# fuente.net
KiCad netlist of a schematic drawn in Altium Designer
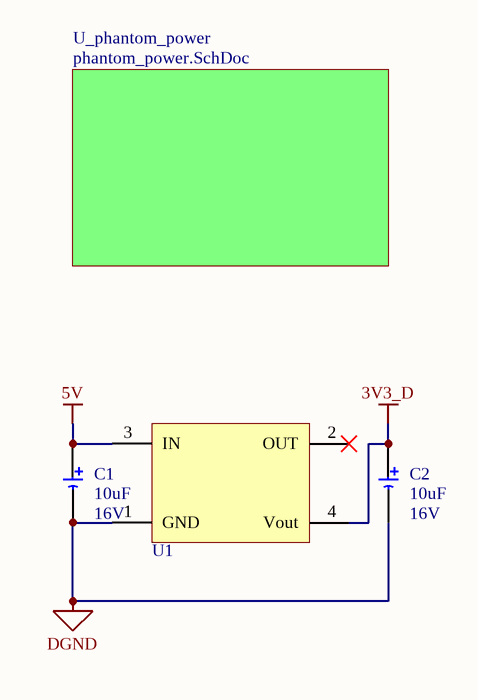
[diagram p0: fuente.SchDoc]

(export (version "E")
  (design (tool "Eeschema 10.0.6"))
  (components
    (comp (ref "C1")
      (value "Capacitor polarizado")
      (footprint "CAP_Electrolytic")
      (fields (field (name "VALOR") "10uF") (field (name "TENSION") "16V"))
      (libsource (lib "sch_comunes") (part "Capacitor polarizado"))
    )
    (comp (ref "C2")
      (value "Capacitor polarizado")
      (footprint "CAP_Electrolytic")
      (fields (field (name "VALOR") "10uF") (field (name "TENSION") "16V"))
      (libsource (lib "sch_comunes") (part "Capacitor polarizado"))
    )
    (comp (ref "U1")
      (value "LM1117")
      (footprint "SOT223")
      (description "LDO Regulator")
      (libsource (lib "Sch_Reguladores") (part "LM1117"))
    )
  )
  (nets
    (net (code "1") (name "3V3_D") (class "Default")
      (node (ref "C2") (pin "1") (pinfunction "1_1") (pintype "passive"))
      (node (ref "U1") (pin "4") (pinfunction "Vout_4") (pintype "passive"))
    )
    (net (code "2") (name "5V") (class "Default")
      (node (ref "C1") (pin "1") (pinfunction "1_1") (pintype "passive"))
      (node (ref "U1") (pin "3") (pinfunction "IN_3") (pintype "passive"))
    )
    (net (code "3") (name "DGND") (class "Default")
      (node (ref "C1") (pin "2") (pinfunction "2_2") (pintype "passive"))
      (node (ref "C2") (pin "2") (pinfunction "2_2") (pintype "passive"))
      (node (ref "U1") (pin "1") (pinfunction "GND_1") (pintype "passive"))
    )
    (net (code "4") (name "unconnected-(U1-OUT-Pad2)") (class "Default")
      (node (ref "U1") (pin "2") (pinfunction "OUT_2") (pintype "passive+no_connect"))
    )
  )
)
